# MOUTING.net
KiCad netlist of a schematic drawn in Altium Designer
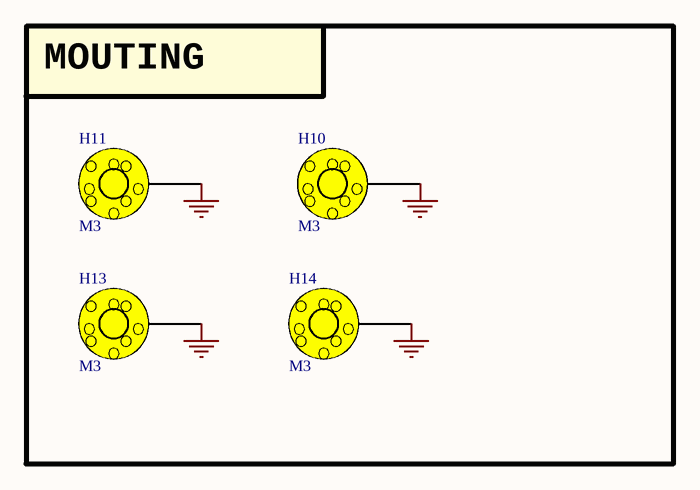
[diagram p0: MOUTING.SchDoc]

(export (version "E")
  (design (tool "Eeschema 10.0.6"))
  (components
    (comp (ref "H10") (value "M3") (footprint "HEX-M3_NoVia") (libsource (lib "hex_M3") (part "HEX-M3")))
    (comp (ref "H11") (value "M3") (footprint "HEX-M3_NoVia") (libsource (lib "hex_M3") (part "HEX-M3")))
    (comp (ref "H13") (value "M3") (footprint "HEX-M3_NoVia") (libsource (lib "hex_M3") (part "HEX-M3")))
    (comp (ref "H14") (value "M3") (footprint "HEX-M3_NoVia") (libsource (lib "hex_M3") (part "HEX-M3")))
  )
  (nets
    (net (code "1") (name "GND") (class "Default")
      (node (ref "H10") (pin "1") (pinfunction "1_1") (pintype "power_in"))
      (node (ref "H11") (pin "1") (pinfunction "1_1") (pintype "power_in"))
      (node (ref "H13") (pin "1") (pinfunction "1_1") (pintype "power_in"))
      (node (ref "H14") (pin "1") (pinfunction "1_1") (pintype "power_in"))
    )
  )
)
